# SCH_ESP8266.net
KiCad netlist of a schematic drawn in Altium Designer
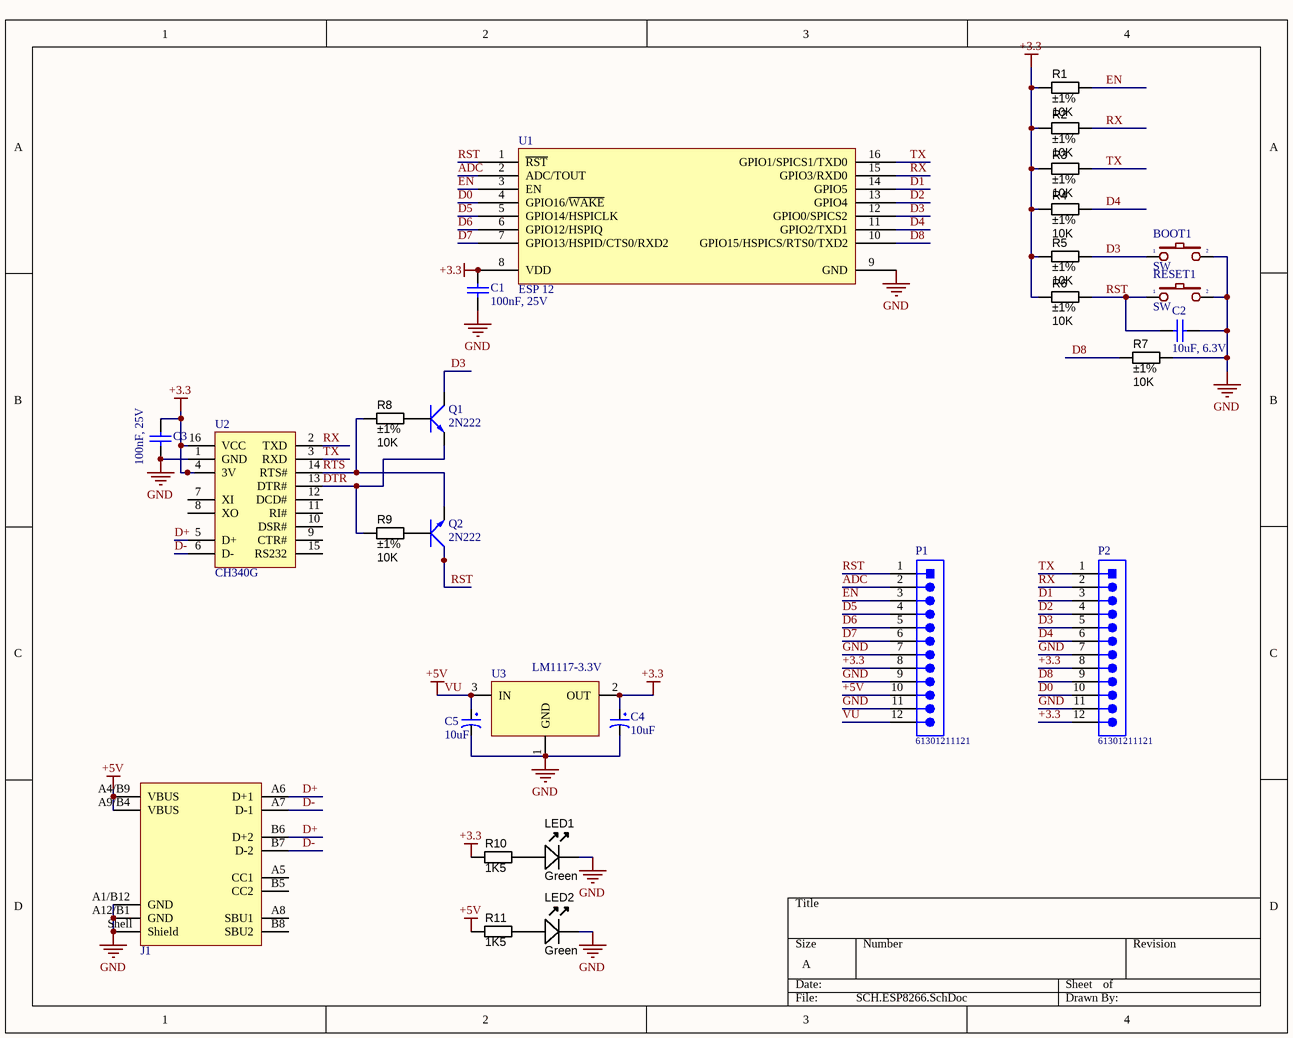
[diagram p0: SCH.ESP8266.SchDoc]

(export (version "E")
  (design (tool "Eeschema 10.0.6"))
  (components
    (comp (ref "BOOT1")
      (value "SW")
      (footprint "SW1-SMD")
      (description "Switch button 2 pin")
      (libsource (lib "Custom Library") (part "SW2"))
    )
    (comp (ref "C1")
      (value "100nF, 25V")
      (footprint "WCAP-CSGP_0603_L1.6W0.8H0.8_Reflow")
      (description "WCAP-CSGP Multilayer Ceramic Chip Capacitor, General Purpose, size 0603, X7R, 100nF, 25V")
      (fields
        (field (name "MANUFACTURER") "Wurth Elektronik")
        (field (name "MANUFACTURER PART NUMBER") "885012206071")
      )
      (libsource (lib "Integrated_Library1") (part "885012206071"))
    )
    (comp (ref "C2")
      (value "10uF, 6.3V")
      (footprint "WCAP-CSGP_0603_L1.6W0.8H0.8_Reflow")
      (description "WCAP-CSGP Multilayer Ceramic Chip Capacitor, General Purpose, size 0603, X5R, 10uF, 6.3V")
      (fields
        (field (name "MANUFACTURER") "Wurth Elektronik")
        (field (name "MANUFACTURER PART NUMBER") "885012106006")
      )
      (libsource (lib "Integrated_Library1") (part "885012106006"))
    )
    (comp (ref "C3")
      (value "100nF, 25V")
      (footprint "WCAP-CSGP_0603_L1.6W0.8H0.8_Reflow")
      (description "WCAP-CSGP Multilayer Ceramic Chip Capacitor, General Purpose, size 0603, X7R, 100nF, 25V")
      (fields
        (field (name "MANUFACTURER") "Wurth Elektronik")
        (field (name "MANUFACTURER PART NUMBER") "885012206071")
      )
      (libsource (lib "Integrated_Library1") (part "885012206071"))
    )
    (comp (ref "C4")
      (value "10uF")
      (footprint "tu tantalum smd3216")
      (description "Dán")
      (libsource (lib "THU VIEN SCH") (part "Tu tantalum 10uF 16V SMD3216"))
    )
    (comp (ref "C5")
      (value "10uF")
      (footprint "tu tantalum smd3216")
      (description "Dán")
      (libsource (lib "THU VIEN SCH") (part "Tu tantalum 10uF 16V SMD3216"))
    )
    (comp (ref "J1")
      (value "629722000214")
      (footprint "629722000214")
      (description "WR-COM USB 2.0 Type C Receptacle Horizontal SMT")
      (fields (field (name "MANUFACTURER") "Wurth Elektronik"))
      (libsource (lib "Altium_WR-USB (rev23b)") (part "629722000214"))
    )
    (comp (ref "LED1")
      (value "Green")
      (footprint "LED-0603-GREEN")
      (description "LED 0603 SMD Green 525nm 350mcd 20mA")
      (libsource (lib "Custom Library") (part "LED_SMD_Green_0603_525nm_350mcd"))
    )
    (comp (ref "LED2")
      (value "Green")
      (footprint "LED-0603-GREEN")
      (description "LED 0603 SMD Green 525nm 350mcd 20mA")
      (libsource (lib "Custom Library") (part "LED_SMD_Green_0603_525nm_350mcd"))
    )
    (comp (ref "P1")
      (value "61301211121")
      (footprint "61301211121")
      (description "WR-PHD Pin Header, THT, pitch 2.54mm, Single Row, Vertical, 12p")
      (fields (field (name "MANUFACTURER") "Wurth Elektronik"))
      (libsource (lib "Integrated_Library1") (part "61301211121"))
    )
    (comp (ref "P2")
      (value "61301211121")
      (footprint "61301211121")
      (description "WR-PHD Pin Header, THT, pitch 2.54mm, Single Row, Vertical, 12p")
      (fields (field (name "MANUFACTURER") "Wurth Elektronik"))
      (libsource (lib "Integrated_Library1") (part "61301211121"))
    )
    (comp (ref "Q1")
      (value "2N222")
      (footprint "SOT23-231")
      (description "NPN 600mW, ECB")
      (libsource (lib "Custom Library") (part "2N222"))
    )
    (comp (ref "Q2")
      (value "2N222")
      (footprint "SOT23-231")
      (description "NPN 600mW, ECB")
      (libsource (lib "Custom Library") (part "2N222"))
    )
    (comp (ref "R1")
      (value "10K")
      (footprint "RESC1608X55N")
      (description "Resistor SMD chip 10k Ohm 0.1W 1% 0603")
      (fields (field (name "TOLERANCE") "±1%") (field (name "Comment") "Thick Film"))
      (libsource (lib "Custom Library") (part "RES_10K_0603_1%"))
    )
    (comp (ref "R2")
      (value "10K")
      (footprint "RESC1608X55N")
      (description "Resistor SMD chip 10k Ohm 0.1W 1% 0603")
      (fields (field (name "TOLERANCE") "±1%") (field (name "Comment") "Thick Film"))
      (libsource (lib "Custom Library") (part "RES_10K_0603_1%"))
    )
    (comp (ref "R3")
      (value "10K")
      (footprint "RESC1608X55N")
      (description "Resistor SMD chip 10k Ohm 0.1W 1% 0603")
      (fields (field (name "TOLERANCE") "±1%") (field (name "Comment") "Thick Film"))
      (libsource (lib "Custom Library") (part "RES_10K_0603_1%"))
    )
    (comp (ref "R4")
      (value "10K")
      (footprint "RESC1608X55N")
      (description "Resistor SMD chip 10k Ohm 0.1W 1% 0603")
      (fields (field (name "TOLERANCE") "±1%") (field (name "Comment") "Thick Film"))
      (libsource (lib "Custom Library") (part "RES_10K_0603_1%"))
    )
    (comp (ref "R5")
      (value "10K")
      (footprint "RESC1608X55N")
      (description "Resistor SMD chip 10k Ohm 0.1W 1% 0603")
      (fields (field (name "TOLERANCE") "±1%") (field (name "Comment") "Thick Film"))
      (libsource (lib "Custom Library") (part "RES_10K_0603_1%"))
    )
    (comp (ref "R6")
      (value "10K")
      (footprint "RESC1608X55N")
      (description "Resistor SMD chip 10k Ohm 0.1W 1% 0603")
      (fields (field (name "TOLERANCE") "±1%") (field (name "Comment") "Thick Film"))
      (libsource (lib "Custom Library") (part "RES_10K_0603_1%"))
    )
    (comp (ref "R7")
      (value "10K")
      (footprint "RESC1608X55N")
      (description "Resistor SMD chip 10k Ohm 0.1W 1% 0603")
      (fields (field (name "TOLERANCE") "±1%") (field (name "Comment") "Thick Film"))
      (libsource (lib "") (part "RES_10K_0603_1%_1"))
    )
    (comp (ref "R8")
      (value "10K")
      (footprint "RESC1608X55N")
      (description "Resistor SMD chip 10k Ohm 0.1W 1% 0603")
      (fields (field (name "TOLERANCE") "±1%") (field (name "Comment") "Thick Film"))
      (libsource (lib "Custom Library") (part "RES_10K_0603_1%"))
    )
    (comp (ref "R9")
      (value "10K")
      (footprint "RESC1608X55N")
      (description "Resistor SMD chip 10k Ohm 0.1W 1% 0603")
      (fields (field (name "TOLERANCE") "±1%") (field (name "Comment") "Thick Film"))
      (libsource (lib "Custom Library") (part "RES_10K_0603_1%"))
    )
    (comp (ref "R10")
      (value "1K5")
      (footprint "RESC1608X55N")
      (description "Resistor SMD chip 1.5k Ohm 0.1W 5% 0603")
      (fields (field (name "TOLERANCE") "±5%") (field (name "Comment") "Thick Film"))
      (libsource (lib "Custom Library") (part "RES_1K5_0603_5%"))
    )
    (comp (ref "R11")
      (value "1K5")
      (footprint "RESC1608X55N")
      (description "Resistor SMD chip 1.5k Ohm 0.1W 5% 0603")
      (fields (field (name "TOLERANCE") "±5%") (field (name "Comment") "Thick Film"))
      (libsource (lib "Custom Library") (part "RES_1K5_0603_5%"))
    )
    (comp (ref "RESET1")
      (value "SW")
      (footprint "SW1-SMD")
      (description "Switch button 2 pin")
      (libsource (lib "Custom Library") (part "SW2"))
    )
    (comp (ref "U1") (value "ESP 12") (footprint "ESP12E") (libsource (lib "myAltium") (part "ESP_12")))
    (comp (ref "U2")
      (value "CH340G")
      (footprint "SO16")
      (description "High and Low Side Driver")
      (fields (field (name "PUBLISHER") "Altium Limited"))
      (libsource (lib "Custom Library") (part "CH340G"))
    )
    (comp (ref "U3")
      (value "LM1117-3.3V")
      (footprint "SOT223")
      (description "800mA Low-Dropout Linear Regulator")
      (fields (field (name "CREATOR") "Nguyen Ba Bien"))
      (libsource (lib "Custom Library") (part "LM1117"))
    )
  )
  (nets
    (net (code "1") (name "+3.3") (class "Default")
      (node (ref "C1") (pin "2") (pinfunction "2_2") (pintype "passive"))
      (node (ref "C3") (pin "2") (pinfunction "2_2") (pintype "passive"))
      (node (ref "C4") (pin "1") (pinfunction "1_1") (pintype "passive"))
      (node (ref "P1") (pin "8") (pinfunction "8_8") (pintype "passive"))
      (node (ref "P2") (pin "12") (pinfunction "12_12") (pintype "passive"))
      (node (ref "P2") (pin "8") (pinfunction "8_8") (pintype "passive"))
      (node (ref "R1") (pin "1") (pinfunction "1_1") (pintype "passive"))
      (node (ref "R10") (pin "1") (pinfunction "1_1") (pintype "passive"))
      (node (ref "R2") (pin "1") (pinfunction "1_1") (pintype "passive"))
      (node (ref "R3") (pin "1") (pinfunction "1_1") (pintype "passive"))
      (node (ref "R4") (pin "1") (pinfunction "1_1") (pintype "passive"))
      (node (ref "R5") (pin "1") (pinfunction "1_1") (pintype "passive"))
      (node (ref "R6") (pin "1") (pinfunction "1_1") (pintype "passive"))
      (node (ref "U1") (pin "8") (pinfunction "VDD_8") (pintype "passive"))
      (node (ref "U2") (pin "16") (pinfunction "VCC_16") (pintype "passive"))
      (node (ref "U2") (pin "4") (pinfunction "3V_4") (pintype "passive"))
      (node (ref "U3") (pin "2") (pinfunction "OUT_2") (pintype "passive"))
    )
    (net (code "2") (name "+5V") (class "Default")
      (node (ref "C5") (pin "1") (pinfunction "1_1") (pintype "passive"))
      (node (ref "J1") (pin "A4/B9") (pinfunction "VBUS_A4/B9") (pintype "passive"))
      (node (ref "J1") (pin "A9/B4") (pinfunction "VBUS_A9/B4") (pintype "passive"))
      (node (ref "P1") (pin "10") (pinfunction "10_10") (pintype "passive"))
      (node (ref "P1") (pin "12") (pinfunction "12_12") (pintype "passive"))
      (node (ref "R11") (pin "1") (pinfunction "1_1") (pintype "passive"))
      (node (ref "U3") (pin "3") (pinfunction "IN_3") (pintype "passive"))
    )
    (net (code "3") (name "/ADC") (class "Default")
      (node (ref "P1") (pin "2") (pinfunction "2_2") (pintype "passive"))
      (node (ref "U1") (pin "2") (pinfunction "ADC/TOUT_2") (pintype "passive"))
    )
    (net (code "4") (name "/D+") (class "Default")
      (node (ref "J1") (pin "A6") (pinfunction "D+1_A6") (pintype "passive"))
      (node (ref "J1") (pin "B6") (pinfunction "D+2_B6") (pintype "passive"))
      (node (ref "U2") (pin "5") (pinfunction "D+_5") (pintype "passive"))
    )
    (net (code "5") (name "/D-") (class "Default")
      (node (ref "J1") (pin "A7") (pinfunction "D-1_A7") (pintype "passive"))
      (node (ref "J1") (pin "B7") (pinfunction "D-2_B7") (pintype "passive"))
      (node (ref "U2") (pin "6") (pinfunction "D-_6") (pintype "passive"))
    )
    (net (code "6") (name "/D0") (class "Default")
      (node (ref "P2") (pin "10") (pinfunction "10_10") (pintype "passive"))
      (node (ref "U1") (pin "4") (pinfunction "GPIO16/~{WAKE}_4") (pintype "passive"))
    )
    (net (code "7") (name "/D1") (class "Default")
      (node (ref "P2") (pin "3") (pinfunction "3_3") (pintype "passive"))
      (node (ref "U1") (pin "14") (pinfunction "GPIO5_14") (pintype "passive"))
    )
    (net (code "8") (name "/D2") (class "Default")
      (node (ref "P2") (pin "4") (pinfunction "4_4") (pintype "passive"))
      (node (ref "U1") (pin "13") (pinfunction "GPIO4_13") (pintype "passive"))
    )
    (net (code "9") (name "/D3") (class "Default")
      (node (ref "BOOT1") (pin "1") (pinfunction "1_1") (pintype "passive"))
      (node (ref "P2") (pin "5") (pinfunction "5_5") (pintype "passive"))
      (node (ref "Q1") (pin "3") (pinfunction "C_3") (pintype "passive"))
      (node (ref "R5") (pin "2") (pinfunction "2_2") (pintype "passive"))
      (node (ref "U1") (pin "12") (pinfunction "GPIO0/SPICS2_12") (pintype "passive"))
    )
    (net (code "10") (name "/D4") (class "Default")
      (node (ref "P2") (pin "6") (pinfunction "6_6") (pintype "passive"))
      (node (ref "R4") (pin "2") (pinfunction "2_2") (pintype "passive"))
      (node (ref "U1") (pin "11") (pinfunction "GPIO2/TXD1_11") (pintype "passive"))
    )
    (net (code "11") (name "/D5") (class "Default")
      (node (ref "P1") (pin "4") (pinfunction "4_4") (pintype "passive"))
      (node (ref "U1") (pin "5") (pinfunction "GPIO14/HSPICLK_5") (pintype "passive"))
    )
    (net (code "12") (name "/D6") (class "Default")
      (node (ref "P1") (pin "5") (pinfunction "5_5") (pintype "passive"))
      (node (ref "U1") (pin "6") (pinfunction "GPIO12/HSPIQ_6") (pintype "passive"))
    )
    (net (code "13") (name "/D7") (class "Default")
      (node (ref "P1") (pin "6") (pinfunction "6_6") (pintype "passive"))
      (node (ref "U1") (pin "7") (pinfunction "GPIO13/HSPID/CTS0/RXD2_7") (pintype "passive"))
    )
    (net (code "14") (name "/D8") (class "Default")
      (node (ref "P2") (pin "9") (pinfunction "9_9") (pintype "passive"))
      (node (ref "R7") (pin "2") (pinfunction "2_2") (pintype "passive"))
      (node (ref "U1") (pin "10") (pinfunction "GPIO15/HSPICS/RTS0/TXD2_10") (pintype "passive"))
    )
    (net (code "15") (name "/DTR") (class "Default")
      (node (ref "Q1") (pin "1") (pinfunction "E_1") (pintype "passive"))
      (node (ref "R9") (pin "1") (pinfunction "1_1") (pintype "passive"))
      (node (ref "U2") (pin "13") (pinfunction "DTR#_13") (pintype "passive"))
    )
    (net (code "16") (name "/EN") (class "Default")
      (node (ref "P1") (pin "3") (pinfunction "3_3") (pintype "passive"))
      (node (ref "R1") (pin "2") (pinfunction "2_2") (pintype "passive"))
      (node (ref "U1") (pin "3") (pinfunction "EN_3") (pintype "passive"))
    )
    (net (code "17") (name "/RST") (class "Default")
      (node (ref "C2") (pin "1") (pinfunction "1_1") (pintype "passive"))
      (node (ref "P1") (pin "1") (pinfunction "1_1") (pintype "passive"))
      (node (ref "Q2") (pin "3") (pinfunction "C_3") (pintype "passive"))
      (node (ref "R6") (pin "2") (pinfunction "2_2") (pintype "passive"))
      (node (ref "RESET1") (pin "1") (pinfunction "1_1") (pintype "passive"))
      (node (ref "U1") (pin "1") (pinfunction "~{RST}_1") (pintype "passive"))
    )
    (net (code "18") (name "/RTS") (class "Default")
      (node (ref "Q2") (pin "1") (pinfunction "E_1") (pintype "passive"))
      (node (ref "R8") (pin "1") (pinfunction "1_1") (pintype "passive"))
      (node (ref "U2") (pin "14") (pinfunction "RTS#_14") (pintype "passive"))
    )
    (net (code "19") (name "/RX") (class "Default")
      (node (ref "P2") (pin "2") (pinfunction "2_2") (pintype "passive"))
      (node (ref "R2") (pin "2") (pinfunction "2_2") (pintype "passive"))
      (node (ref "U1") (pin "15") (pinfunction "GPIO3/RXD0_15") (pintype "passive"))
      (node (ref "U2") (pin "2") (pinfunction "TXD_2") (pintype "passive"))
    )
    (net (code "20") (name "/TX") (class "Default")
      (node (ref "P2") (pin "1") (pinfunction "1_1") (pintype "passive"))
      (node (ref "R3") (pin "2") (pinfunction "2_2") (pintype "passive"))
      (node (ref "U1") (pin "16") (pinfunction "GPIO1/SPICS1/TXD0_16") (pintype "passive"))
      (node (ref "U2") (pin "3") (pinfunction "RXD_3") (pintype "passive"))
    )
    (net (code "21") (name "GND") (class "Default")
      (node (ref "BOOT1") (pin "2") (pinfunction "2_2") (pintype "passive"))
      (node (ref "C1") (pin "1") (pinfunction "1_1") (pintype "passive"))
      (node (ref "C2") (pin "2") (pinfunction "2_2") (pintype "passive"))
      (node (ref "C3") (pin "1") (pinfunction "1_1") (pintype "passive"))
      (node (ref "C4") (pin "2") (pinfunction "2_2") (pintype "passive"))
      (node (ref "C5") (pin "2") (pinfunction "2_2") (pintype "passive"))
      (node (ref "J1") (pin "A1/B12") (pinfunction "GND_A1/B12") (pintype "passive"))
      (node (ref "J1") (pin "A12/B1") (pinfunction "GND_A12/B1") (pintype "passive"))
      (node (ref "J1") (pin "Shell") (pinfunction "Shield_Shell") (pintype "passive"))
      (node (ref "LED1") (pin "K") (pinfunction "K_K") (pintype "passive"))
      (node (ref "LED2") (pin "K") (pinfunction "K_K") (pintype "passive"))
      (node (ref "P1") (pin "11") (pinfunction "11_11") (pintype "passive"))
      (node (ref "P1") (pin "7") (pinfunction "7_7") (pintype "passive"))
      (node (ref "P1") (pin "9") (pinfunction "9_9") (pintype "passive"))
      (node (ref "P2") (pin "11") (pinfunction "11_11") (pintype "passive"))
      (node (ref "P2") (pin "7") (pinfunction "7_7") (pintype "passive"))
      (node (ref "R7") (pin "1") (pinfunction "1_1") (pintype "passive"))
      (node (ref "RESET1") (pin "2") (pinfunction "2_2") (pintype "passive"))
      (node (ref "U1") (pin "9") (pinfunction "GND_9") (pintype "passive"))
      (node (ref "U2") (pin "1") (pinfunction "GND_1") (pintype "passive"))
      (node (ref "U3") (pin "1") (pinfunction "GND_1") (pintype "passive"))
    )
    (net (code "22") (name "Net-(LED1-PadA)") (class "Default")
      (node (ref "LED1") (pin "A") (pinfunction "A_A") (pintype "passive"))
      (node (ref "R10") (pin "2") (pinfunction "2_2") (pintype "passive"))
    )
    (net (code "23") (name "Net-(LED2-PadA)") (class "Default")
      (node (ref "LED2") (pin "A") (pinfunction "A_A") (pintype "passive"))
      (node (ref "R11") (pin "2") (pinfunction "2_2") (pintype "passive"))
    )
    (net (code "24") (name "Net-(Q1-B)") (class "Default")
      (node (ref "Q1") (pin "2") (pinfunction "B_2") (pintype "passive"))
      (node (ref "R8") (pin "2") (pinfunction "2_2") (pintype "passive"))
    )
    (net (code "25") (name "Net-(Q2-B)") (class "Default")
      (node (ref "Q2") (pin "2") (pinfunction "B_2") (pintype "passive"))
      (node (ref "R9") (pin "2") (pinfunction "2_2") (pintype "passive"))
    )
    (net (code "26") (name "unconnected-(J1-CC1-PadA5)") (class "Default")
      (node (ref "J1") (pin "A5") (pinfunction "CC1_A5") (pintype "passive"))
    )
    (net (code "27") (name "unconnected-(J1-CC2-PadB5)") (class "Default")
      (node (ref "J1") (pin "B5") (pinfunction "CC2_B5") (pintype "passive"))
    )
    (net (code "28") (name "unconnected-(J1-SBU1-PadA8)") (class "Default")
      (node (ref "J1") (pin "A8") (pinfunction "SBU1_A8") (pintype "passive"))
    )
    (net (code "29") (name "unconnected-(J1-SBU2-PadB8)") (class "Default")
      (node (ref "J1") (pin "B8") (pinfunction "SBU2_B8") (pintype "passive"))
    )
    (net (code "30") (name "unconnected-(U2-CTR#-Pad9)") (class "Default")
      (node (ref "U2") (pin "9") (pinfunction "CTR#_9") (pintype "passive"))
    )
    (net (code "31") (name "unconnected-(U2-DCD#-Pad12)") (class "Default")
      (node (ref "U2") (pin "12") (pinfunction "DCD#_12") (pintype "passive"))
    )
    (net (code "32") (name "unconnected-(U2-DSR#-Pad10)") (class "Default")
      (node (ref "U2") (pin "10") (pinfunction "DSR#_10") (pintype "passive"))
    )
    (net (code "33") (name "unconnected-(U2-RI#-Pad11)") (class "Default")
      (node (ref "U2") (pin "11") (pinfunction "RI#_11") (pintype "passive"))
    )
    (net (code "34") (name "unconnected-(U2-RS232-Pad15)") (class "Default")
      (node (ref "U2") (pin "15") (pinfunction "RS232_15") (pintype "passive"))
    )
    (net (code "35") (name "unconnected-(U2-XI-Pad7)") (class "Default")
      (node (ref "U2") (pin "7") (pinfunction "XI_7") (pintype "passive"))
    )
    (net (code "36") (name "unconnected-(U2-XO-Pad8)") (class "Default")
      (node (ref "U2") (pin "8") (pinfunction "XO_8") (pintype "passive"))
    )
  )
)
